# BulbCommander2.net
KiCad netlist of a schematic drawn in Altium Designer
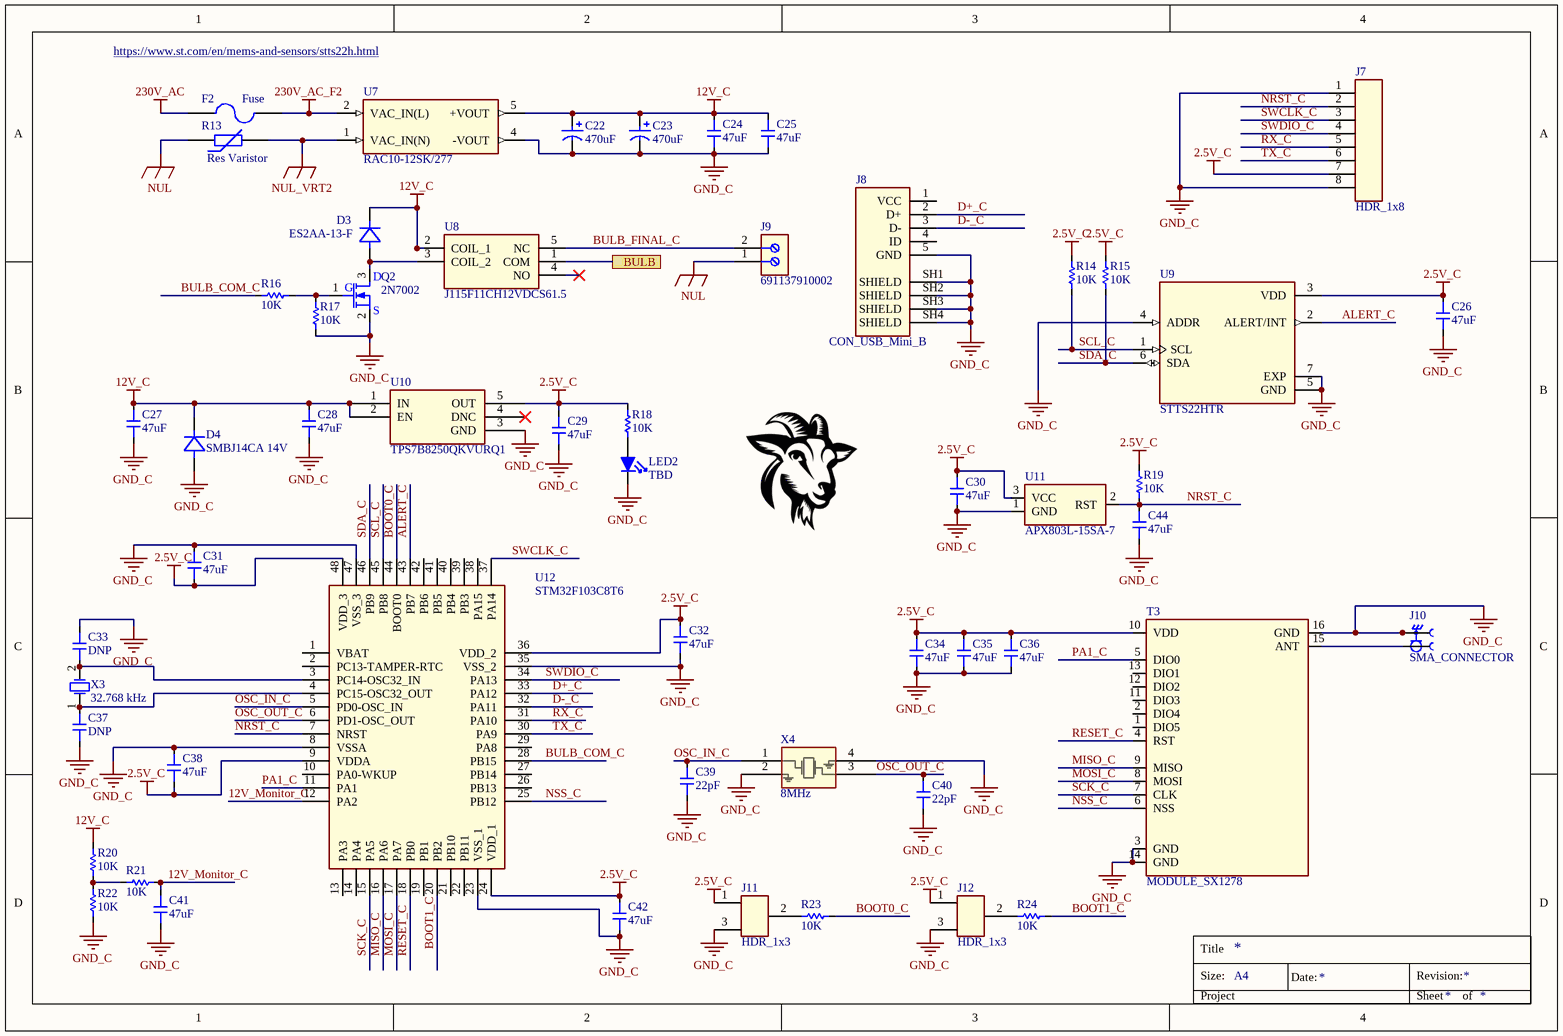
[diagram p0: BulbCommander2.SchDoc]

(export (version "E")
  (design (tool "Eeschema 10.0.6"))
  (components
    (comp (ref "C22")
      (value "470uF")
      (footprint "WCAP-ASLL_D16H17")
      (description "Capacitor_Pol_470uF")
      (fields (field (name "Comment") "Cap Pol1") (field (name "PUBLISHER") "Altium Limited"))
      (libsource (lib "BulbCommander") (part "Capacitor_Pol_470uF"))
    )
    (comp (ref "C23")
      (value "470uF")
      (footprint "WCAP-ASLL_D16H17")
      (description "Capacitor_Pol_470uF")
      (fields (field (name "Comment") "Cap Pol1") (field (name "PUBLISHER") "Altium Limited"))
      (libsource (lib "BulbCommander") (part "Capacitor_Pol_470uF"))
    )
    (comp (ref "C24")
      (value "47uF")
      (footprint "2220")
      (description "CAP CER 47uF 20% 35V X7R 2220")
      (fields (field (name "MFR") "TBD"))
      (libsource (lib "BulbCommander") (part "Capacitor_47uF_2220"))
    )
    (comp (ref "C25")
      (value "47uF")
      (footprint "2220")
      (description "CAP CER 47uF 20% 35V X7R 2220")
      (fields (field (name "MFR") "TBD"))
      (libsource (lib "BulbCommander") (part "Capacitor_47uF_2220"))
    )
    (comp (ref "C26")
      (value "47uF")
      (footprint "CASE0603")
      (description "CAP CER 47uF 20% 35V X7R 2220")
      (fields (field (name "MFR") "TBD"))
      (libsource (lib "BulbCommander") (part "Capacitor_47uF_1206"))
    )
    (comp (ref "C27")
      (value "47uF")
      (footprint "1206")
      (description "CAP CER 47uF 20% 35V X7R 2220")
      (fields (field (name "MFR") "TBD"))
      (libsource (lib "BulbCommander") (part "Capacitor_47uF_1206"))
    )
    (comp (ref "C28")
      (value "47uF")
      (footprint "1206")
      (description "CAP CER 47uF 20% 35V X7R 2220")
      (fields (field (name "MFR") "TBD"))
      (libsource (lib "BulbCommander") (part "Capacitor_47uF_1206"))
    )
    (comp (ref "C29")
      (value "47uF")
      (footprint "1206")
      (description "CAP CER 47uF 20% 35V X7R 2220")
      (fields (field (name "MFR") "TBD"))
      (libsource (lib "BulbCommander") (part "Capacitor_47uF_1206"))
    )
    (comp (ref "C30")
      (value "47uF")
      (footprint "CASE0603")
      (description "CAP CER 47uF 20% 35V X7R 2220")
      (fields (field (name "MFR") "TBD"))
      (libsource (lib "BulbCommander") (part "Capacitor_47uF_1206"))
    )
    (comp (ref "C31")
      (value "47uF")
      (footprint "CASE0603")
      (description "CAP CER 47uF 20% 35V X7R 2220")
      (fields (field (name "MFR") "TBD"))
      (libsource (lib "BulbCommander") (part "Capacitor_47uF_1206"))
    )
    (comp (ref "C32")
      (value "47uF")
      (footprint "CASE0603")
      (description "CAP CER 47uF 20% 35V X7R 2220")
      (fields (field (name "MFR") "TBD"))
      (libsource (lib "BulbCommander") (part "Capacitor_47uF_1206"))
    )
    (comp (ref "C33")
      (value "DNP")
      (footprint "CASE0603")
      (description "CAP CER 47uF 20% 35V X7R 2220")
      (fields (field (name "MFR") "TBD"))
      (libsource (lib "BulbCommander") (part "Capacitor_47uF_0603"))
    )
    (comp (ref "C34")
      (value "47uF")
      (footprint "CASE0603")
      (description "CAP CER 47uF 20% 35V X7R 2220")
      (fields (field (name "MFR") "TBD"))
      (libsource (lib "BulbCommander") (part "Capacitor_47uF_1206"))
    )
    (comp (ref "C35")
      (value "47uF")
      (footprint "CASE0603")
      (description "CAP CER 47uF 20% 35V X7R 2220")
      (fields (field (name "MFR") "TBD"))
      (libsource (lib "BulbCommander") (part "Capacitor_47uF_1206"))
    )
    (comp (ref "C36")
      (value "47uF")
      (footprint "CASE0603")
      (description "CAP CER 47uF 20% 35V X7R 2220")
      (fields (field (name "MFR") "TBD"))
      (libsource (lib "BulbCommander") (part "Capacitor_47uF_1206"))
    )
    (comp (ref "C37")
      (value "DNP")
      (footprint "CASE0603")
      (description "CAP CER 47uF 20% 35V X7R 2220")
      (fields (field (name "MFR") "TBD"))
      (libsource (lib "BulbCommander") (part "Capacitor_47uF_0603"))
    )
    (comp (ref "C38")
      (value "47uF")
      (footprint "CASE0603")
      (description "CAP CER 47uF 20% 35V X7R 2220")
      (fields (field (name "MFR") "TBD"))
      (libsource (lib "BulbCommander") (part "Capacitor_47uF_1206"))
    )
    (comp (ref "C39")
      (value "22pF")
      (footprint "CASE0603")
      (description "CAP CER 47uF 20% 35V X7R 2220")
      (fields (field (name "MFR") "TBD"))
      (libsource (lib "BulbCommander") (part "Capacitor_47uF_1206"))
    )
    (comp (ref "C40")
      (value "22pF")
      (footprint "CASE0603")
      (description "CAP CER 47uF 20% 35V X7R 2220")
      (fields (field (name "MFR") "TBD"))
      (libsource (lib "BulbCommander") (part "Capacitor_47uF_1206"))
    )
    (comp (ref "C41")
      (value "47uF")
      (footprint "CASE0603")
      (description "CAP CER 47uF 20% 35V X7R 2220")
      (fields (field (name "MFR") "TBD"))
      (libsource (lib "BulbCommander") (part "Capacitor_47uF_1206"))
    )
    (comp (ref "C42")
      (value "47uF")
      (footprint "CASE0603")
      (description "CAP CER 47uF 20% 35V X7R 2220")
      (fields (field (name "MFR") "TBD"))
      (libsource (lib "BulbCommander") (part "Capacitor_47uF_1206"))
    )
    (comp (ref "C44")
      (value "47uF")
      (footprint "CASE0603")
      (description "CAP CER 47uF 20% 35V X7R 2220")
      (fields (field (name "MFR") "TBD"))
      (libsource (lib "BulbCommander") (part "Capacitor_47uF_1206"))
    )
    (comp (ref "D3")
      (value "ES2AA-13-F")
      (footprint "SMA_DIODE")
      (description "DIODE STANDARD 50V 2A SMA")
      (fields (field (name "MFR") "Diodes Incoprated"))
      (libsource (lib "BulbCommander") (part "Diode_SMA"))
    )
    (comp (ref "D4")
      (value "SMBJ14CA 14V")
      (footprint "SMBJSeries_LTF-M")
      (description "SMBJ14CA TVS DIODE 14V")
      (libsource (lib "BulbCommander") (part "Diode_SMBJ14CA"))
    )
    (comp (ref "F2")
      (value "Fuse")
      (footprint "FUSE")
      (fields (field (name "PUBLISHER") "Altium Limited"))
      (libsource (lib "BulbCommander") (part "Fuse"))
    )
    (comp (ref "J7")
      (value "HDR_1x8")
      (footprint "Header_1x8_2.54_Male")
      (description "HDR MALE 2.54MM PCB")
      (fields (field (name "MFR") "Wurth"))
      (libsource (lib "BulbCommander") (part "HDR_1x8"))
    )
    (comp (ref "J8")
      (value "CON_USB_Mini_B")
      (footprint "CUI_UJ2-MBH-4-SMT")
      (description "USB B mini")
      (fields (field (name "MFR") "Same Sky"))
      (libsource (lib "BulbCommander") (part "CON_USB_Mini_B"))
    )
    (comp (ref "J9")
      (value "691137910002")
      (footprint "691137910002")
      (description "TERM BLOCK 2P HORIZON 7.5MM PCB")
      (fields (field (name "MFR") "Wurth"))
      (libsource (lib "BulbCommander") (part "CON_1x2"))
    )
    (comp (ref "J10")
      (value "SMA_CONNECTOR")
      (footprint "LPRS_SMA_CONNECTOR")
      (description "Straight SMA Connector")
      (fields (field (name "MP") "altium_native_batch"))
      (libsource (lib "BulbCommander") (part "SMA_CONNECTOR"))
    )
    (comp (ref "J11")
      (value "HDR_1x3")
      (footprint "Header_1x3_2.54_Male")
      (description "HDR MALE 3 x 2.54MM PCB")
      (fields (field (name "MFR") "Wurth"))
      (libsource (lib "BulbCommander") (part "HDR_1x3"))
    )
    (comp (ref "J12")
      (value "HDR_1x3")
      (footprint "Header_1x3_2.54_Male")
      (description "HDR MALE 3 x 2.54MM PCB")
      (fields (field (name "MFR") "Wurth"))
      (libsource (lib "BulbCommander") (part "HDR_1x3"))
    )
    (comp (ref "LED2")
      (value "TBD")
      (footprint "CASE0603")
      (description "Typical INFRARED GaAs LED")
      (libsource (lib "BulbCommander") (part "LED"))
    )
    (comp (ref "Q2")
      (value "2N7002")
      (footprint "SOT23-3")
      (description "MOSFET N-CH 60V 280MA SOT23-3")
      (fields (field (name "MFR") "Microchip"))
      (libsource (lib "BulbCommander") (part "Transistor_NMOS"))
    )
    (comp (ref "R13")
      (value "Res Varistor")
      (footprint "AXIAL-0.3")
      (description "Varistor (Voltage-Sensitive Resistor)")
      (fields (field (name "PUBLISHER") "Altium Limited"))
      (libsource (lib "BulbCommander") (part "Res Varistor"))
    )
    (comp (ref "R14")
      (value "10K")
      (footprint "CASE0603")
      (description "RES 10K 1% 1/10W 0603")
      (fields (field (name "MFR") "YAGEO"))
      (libsource (lib "BulbCommander") (part "Resistor_10K_0603"))
    )
    (comp (ref "R15")
      (value "10K")
      (footprint "CASE0603")
      (description "RES 10K 1% 1/10W 0603")
      (fields (field (name "MFR") "YAGEO"))
      (libsource (lib "BulbCommander") (part "Resistor_10K_0603"))
    )
    (comp (ref "R16")
      (value "10K")
      (footprint "CASE0603")
      (description "RES 10K 1% 1/10W 0603")
      (fields (field (name "MFR") "YAGEO"))
      (libsource (lib "BulbCommander") (part "Resistor_10K_0603"))
    )
    (comp (ref "R17")
      (value "10K")
      (footprint "CASE0603")
      (description "RES 10K 1% 1/10W 0603")
      (fields (field (name "MFR") "YAGEO"))
      (libsource (lib "BulbCommander") (part "Resistor_10K_0603"))
    )
    (comp (ref "R18")
      (value "10K")
      (footprint "CASE0603")
      (description "RES 10K 1% 1/10W 0603")
      (fields (field (name "MFR") "YAGEO"))
      (libsource (lib "BulbCommander") (part "Resistor_10K_0603"))
    )
    (comp (ref "R19")
      (value "10K")
      (footprint "CASE0603")
      (description "RES 10K 1% 1/10W 0603")
      (fields (field (name "MFR") "YAGEO"))
      (libsource (lib "BulbCommander") (part "Resistor_10K_0603"))
    )
    (comp (ref "R20")
      (value "10K")
      (footprint "CASE0603")
      (description "RES 10K 1% 1/10W 0603")
      (fields (field (name "MFR") "YAGEO"))
      (libsource (lib "BulbCommander") (part "Resistor_10K_0603"))
    )
    (comp (ref "R21")
      (value "10K")
      (footprint "CASE0603")
      (description "RES 10K 1% 1/10W 0603")
      (fields (field (name "MFR") "YAGEO"))
      (libsource (lib "BulbCommander") (part "Resistor_10K_0603"))
    )
    (comp (ref "R22")
      (value "10K")
      (footprint "CASE0603")
      (description "RES 10K 1% 1/10W 0603")
      (fields (field (name "MFR") "YAGEO"))
      (libsource (lib "BulbCommander") (part "Resistor_10K_0603"))
    )
    (comp (ref "R23")
      (value "10K")
      (footprint "CASE0603")
      (description "RES 10K 1% 1/10W 0603")
      (fields (field (name "MFR") "YAGEO"))
      (libsource (lib "BulbCommander") (part "Resistor_10K_0603"))
    )
    (comp (ref "R24")
      (value "10K")
      (footprint "CASE0603")
      (description "RES 10K 1% 1/10W 0603")
      (fields (field (name "MFR") "YAGEO"))
      (libsource (lib "BulbCommander") (part "Resistor_10K_0603"))
    )
    (comp (ref "T3")
      (value "MODULE_SX1278")
      (footprint "LORA SX1278")
      (description "MODULE_SX1278 LORA 433 MHz")
      (fields (field (name "MFR") "LORA"))
      (libsource (lib "BulbCommander") (part "MODULE_SX1278"))
    )
    (comp (ref "U7")
      (value "RAC10-12SK/277")
      (footprint "CONV_RAC10-12SK/277")
      (description "AC/DC CONVERTER 12V 10W")
      (fields (field (name "MFR") "RECOM"))
      (libsource (lib "BulbCommander") (part "CONV_RAC10-12SK/277"))
    )
    (comp (ref "U8")
      (value "J115F11CH12VDCS61.5")
      (footprint "J115F11CH12VDCS615U")
      (description "RELAY GEN PURPOSE SPDT 50A 12V")
      (fields (field (name "MFR") "CIT Relay and Switch"))
      (libsource (lib "BulbCommander") (part "RELAY_J115F11CH12VDCS61.5"))
    )
    (comp (ref "U9")
      (value "STTS22HTR")
      (footprint "Sensor_6-UDFN")
      (description "Low-voltage, ultralow-power, 0.5°C accuracy I²C/SMBus 3.0 temperature sensor")
      (fields (field (name "MFR") "STMicroelectronics"))
      (libsource (lib "BulbCommander") (part "SENSOR_STTS22HTR"))
    )
    (comp (ref "U10")
      (value "TPS7B8250QKVURQ1")
      (footprint "SOT_QKVURQ1_TEX")
      (fields (field (name "MFR") "Texas Instruments"))
      (libsource (lib "BulbCommander") (part "CONV_LDO_TPS7B8250QKVURQ1"))
    )
    (comp (ref "U11")
      (value "APX803L-15SA-7")
      (footprint "SOT23-3")
      (description "Supervisor Open Drain or Open Collector 1 Channel SOT-23-3")
      (fields (field (name "MFR") "Diodes Incorporated"))
      (libsource (lib "BulbCommander") (part "IC_APX803L-15SA-7"))
    )
    (comp (ref "U12")
      (value "STM32F103C8T6")
      (footprint "QFP50P900X900X160-48N")
      (description "IC MCU 32BIT 64KB FLASH 48LQFP")
      (fields (field (name "MFR") "STMicroelectronics"))
      (libsource (lib "BulbCommander") (part "IC_STM32F103C8T6"))
    )
    (comp (ref "X3")
      (value "32.768 kHz")
      (footprint "XTAL_ECS-.327-12.5-34B-C-TR")
      (description "32.768 kHz ±10ppm Crystal 12.5pF 70 kOhms 2-SMD, No Lead")
      (fields (field (name "MFR") "ECS"))
      (libsource (lib "BulbCommander") (part "Crystal_ECS-.327-12.5-34B-C-TR"))
    )
    (comp (ref "X4")
      (value "8MHz")
      (footprint "XTAL4P_ABM3B_ABR")
      (description "8 MHz Crystal")
      (fields (field (name "MFR") "Abracon"))
      (libsource (lib "BulbCommander") (part "ABM3B-8.000MHZ-10-1UT"))
    )
  )
  (nets
    (net (code "1") (name "/12V_Monitor_C") (class "Default")
      (node (ref "C41") (pin "1") (pinfunction "1_1") (pintype "passive"))
      (node (ref "R21") (pin "2") (pinfunction "2_2") (pintype "passive"))
      (node (ref "U12") (pin "12") (pinfunction "PA2_12") (pintype "passive"))
    )
    (net (code "2") (name "/ALERT_C") (class "Default")
      (node (ref "U12") (pin "43") (pinfunction "PB7_43") (pintype "passive"))
      (node (ref "U9") (pin "2") (pinfunction "ALERT/INT_2") (pintype "output"))
    )
    (net (code "3") (name "/BOOT0_C") (class "Default")
      (node (ref "R23") (pin "1") (pinfunction "1_1") (pintype "passive"))
      (node (ref "U12") (pin "44") (pinfunction "BOOT0_44") (pintype "passive"))
    )
    (net (code "4") (name "/BOOT1_C") (class "Default")
      (node (ref "R24") (pin "1") (pinfunction "1_1") (pintype "passive"))
      (node (ref "U12") (pin "20") (pinfunction "PB2_20") (pintype "passive"))
    )
    (net (code "5") (name "/BULB") (class "Default")
      (node (ref "U8") (pin "1") (pinfunction "COM_1") (pintype "passive"))
    )
    (net (code "6") (name "/BULB_COM_C") (class "Default")
      (node (ref "R16") (pin "2") (pinfunction "2_2") (pintype "passive"))
      (node (ref "U12") (pin "28") (pinfunction "PB15_28") (pintype "passive"))
    )
    (net (code "7") (name "/BULB_FINAL_C") (class "Default")
      (node (ref "J9") (pin "2") (pinfunction "2_2") (pintype "passive"))
      (node (ref "U8") (pin "5") (pinfunction "NC_5") (pintype "passive"))
    )
    (net (code "8") (name "/D+_C") (class "Default")
      (node (ref "J8") (pin "2") (pinfunction "D+_2") (pintype "passive"))
      (node (ref "U12") (pin "33") (pinfunction "PA12_33") (pintype "passive"))
    )
    (net (code "9") (name "/D-_C") (class "Default")
      (node (ref "J8") (pin "3") (pinfunction "D-_3") (pintype "passive"))
      (node (ref "U12") (pin "32") (pinfunction "PA11_32") (pintype "passive"))
    )
    (net (code "10") (name "/MISO_C") (class "Default")
      (node (ref "T3") (pin "9") (pinfunction "MISO_9") (pintype "passive"))
      (node (ref "U12") (pin "16") (pinfunction "PA6_16") (pintype "passive"))
    )
    (net (code "11") (name "/MOSI_C") (class "Default")
      (node (ref "T3") (pin "8") (pinfunction "MOSI_8") (pintype "passive"))
      (node (ref "U12") (pin "17") (pinfunction "PA7_17") (pintype "passive"))
    )
    (net (code "12") (name "/NRST_C") (class "Default")
      (node (ref "C44") (pin "2") (pinfunction "2_2") (pintype "passive"))
      (node (ref "J7") (pin "2") (pinfunction "2_2") (pintype "passive"))
      (node (ref "R19") (pin "1") (pinfunction "1_1") (pintype "passive"))
      (node (ref "U11") (pin "2") (pinfunction "RST_2") (pintype "passive"))
      (node (ref "U12") (pin "7") (pinfunction "NRST_7") (pintype "passive"))
    )
    (net (code "13") (name "/NSS_C") (class "Default")
      (node (ref "T3") (pin "6") (pinfunction "NSS_6") (pintype "passive"))
      (node (ref "U12") (pin "25") (pinfunction "PB12_25") (pintype "passive"))
    )
    (net (code "14") (name "/OSC_IN_C") (class "Default")
      (node (ref "C39") (pin "1") (pinfunction "1_1") (pintype "passive"))
      (node (ref "U12") (pin "5") (pinfunction "PD0-OSC_IN_5") (pintype "passive"))
      (node (ref "X4") (pin "1") (pinfunction "1_1") (pintype "passive"))
    )
    (net (code "15") (name "/OSC_OUT_C") (class "Default")
      (node (ref "C40") (pin "1") (pinfunction "1_1") (pintype "passive"))
      (node (ref "U12") (pin "6") (pinfunction "PD1-OSC_OUT_6") (pintype "passive"))
      (node (ref "X4") (pin "3") (pinfunction "3_3") (pintype "passive"))
    )
    (net (code "16") (name "/PA1_C") (class "Default")
      (node (ref "T3") (pin "5") (pinfunction "DIO0_5") (pintype "passive"))
      (node (ref "U12") (pin "11") (pinfunction "PA1_11") (pintype "passive"))
    )
    (net (code "17") (name "/RESET_C") (class "Default")
      (node (ref "T3") (pin "4") (pinfunction "RST_4") (pintype "passive"))
      (node (ref "U12") (pin "18") (pinfunction "PB0_18") (pintype "passive"))
    )
    (net (code "18") (name "/RX_C") (class "Default")
      (node (ref "J7") (pin "5") (pinfunction "5_5") (pintype "passive"))
      (node (ref "U12") (pin "31") (pinfunction "PA10_31") (pintype "passive"))
    )
    (net (code "19") (name "/SCK_C") (class "Default")
      (node (ref "T3") (pin "7") (pinfunction "CLK_7") (pintype "passive"))
      (node (ref "U12") (pin "15") (pinfunction "PA5_15") (pintype "passive"))
    )
    (net (code "20") (name "/SCL_C") (class "Default")
      (node (ref "R14") (pin "1") (pinfunction "1_1") (pintype "passive"))
      (node (ref "U12") (pin "45") (pinfunction "PB8_45") (pintype "passive"))
      (node (ref "U9") (pin "1") (pinfunction "SCL_1") (pintype "input"))
    )
    (net (code "21") (name "/SDA_C") (class "Default")
      (node (ref "R15") (pin "1") (pinfunction "1_1") (pintype "passive"))
      (node (ref "U12") (pin "46") (pinfunction "PB9_46") (pintype "passive"))
      (node (ref "U9") (pin "6") (pinfunction "SDA_6") (pintype "bidirectional"))
    )
    (net (code "22") (name "/SWCLK_C") (class "Default")
      (node (ref "J7") (pin "3") (pinfunction "3_3") (pintype "passive"))
      (node (ref "U12") (pin "37") (pinfunction "PA14_37") (pintype "passive"))
    )
    (net (code "23") (name "/SWDIO_C") (class "Default")
      (node (ref "J7") (pin "4") (pinfunction "4_4") (pintype "passive"))
      (node (ref "U12") (pin "34") (pinfunction "PA13_34") (pintype "passive"))
    )
    (net (code "24") (name "/TX_C") (class "Default")
      (node (ref "J7") (pin "6") (pinfunction "6_6") (pintype "passive"))
      (node (ref "U12") (pin "30") (pinfunction "PA9_30") (pintype "passive"))
    )
    (net (code "25") (name "2.5V_C") (class "Default")
      (node (ref "C26") (pin "2") (pinfunction "2_2") (pintype "passive"))
      (node (ref "C29") (pin "2") (pinfunction "2_2") (pintype "passive"))
      (node (ref "C30") (pin "2") (pinfunction "2_2") (pintype "passive"))
      (node (ref "C31") (pin "1") (pinfunction "1_1") (pintype "passive"))
      (node (ref "C32") (pin "2") (pinfunction "2_2") (pintype "passive"))
      (node (ref "C34") (pin "2") (pinfunction "2_2") (pintype "passive"))
      (node (ref "C35") (pin "2") (pinfunction "2_2") (pintype "passive"))
      (node (ref "C36") (pin "2") (pinfunction "2_2") (pintype "passive"))
      (node (ref "C38") (pin "2") (pinfunction "2_2") (pintype "passive"))
      (node (ref "C42") (pin "2") (pinfunction "2_2") (pintype "passive"))
      (node (ref "J11") (pin "1") (pinfunction "1_1") (pintype "passive"))
      (node (ref "J12") (pin "1") (pinfunction "1_1") (pintype "passive"))
      (node (ref "J7") (pin "7") (pinfunction "7_7") (pintype "passive"))
      (node (ref "R14") (pin "2") (pinfunction "2_2") (pintype "passive"))
      (node (ref "R15") (pin "2") (pinfunction "2_2") (pintype "passive"))
      (node (ref "R18") (pin "2") (pinfunction "2_2") (pintype "passive"))
      (node (ref "R19") (pin "2") (pinfunction "2_2") (pintype "passive"))
      (node (ref "T3") (pin "10") (pinfunction "VDD_10") (pintype "passive"))
      (node (ref "U10") (pin "5") (pinfunction "OUT_5") (pintype "passive"))
      (node (ref "U11") (pin "3") (pinfunction "VCC_3") (pintype "passive"))
      (node (ref "U12") (pin "24") (pinfunction "VDD_1_24") (pintype "passive"))
      (node (ref "U12") (pin "36") (pinfunction "VDD_2_36") (pintype "passive"))
      (node (ref "U12") (pin "48") (pinfunction "VDD_3_48") (pintype "passive"))
      (node (ref "U12") (pin "9") (pinfunction "VDDA_9") (pintype "passive"))
      (node (ref "U9") (pin "3") (pinfunction "VDD_3") (pintype "power_in"))
    )
    (net (code "26") (name "12V_C") (class "Default")
      (node (ref "C22") (pin "1") (pinfunction "1_1") (pintype "passive"))
      (node (ref "C23") (pin "1") (pinfunction "1_1") (pintype "passive"))
      (node (ref "C24") (pin "2") (pinfunction "2_2") (pintype "passive"))
      (node (ref "C25") (pin "2") (pinfunction "2_2") (pintype "passive"))
      (node (ref "C27") (pin "2") (pinfunction "2_2") (pintype "passive"))
      (node (ref "C28") (pin "2") (pinfunction "2_2") (pintype "passive"))
      (node (ref "D3") (pin "1") (pinfunction "1_1") (pintype "passive"))
      (node (ref "D4") (pin "1") (pinfunction "1_1") (pintype "passive"))
      (node (ref "R20") (pin "2") (pinfunction "2_2") (pintype "passive"))
      (node (ref "U10") (pin "1") (pinfunction "IN_1") (pintype "passive"))
      (node (ref "U10") (pin "2") (pinfunction "EN_2") (pintype "passive"))
      (node (ref "U7") (pin "5") (pinfunction "+VOUT_5") (pintype "output"))
      (node (ref "U8") (pin "2") (pinfunction "COIL_1_2") (pintype "passive"))
    )
    (net (code "27") (name "230V_AC") (class "Default")
      (node (ref "F2") (pin "1") (pinfunction "1_1") (pintype "passive"))
    )
    (net (code "28") (name "230V_AC_F2") (class "Default")
      (node (ref "F2") (pin "2") (pinfunction "2_2") (pintype "passive"))
      (node (ref "U7") (pin "2") (pinfunction "VAC_IN(L)_2") (pintype "input"))
    )
    (net (code "29") (name "GND_C") (class "Default")
      (node (ref "C22") (pin "2") (pinfunction "2_2") (pintype "passive"))
      (node (ref "C23") (pin "2") (pinfunction "2_2") (pintype "passive"))
      (node (ref "C24") (pin "1") (pinfunction "1_1") (pintype "passive"))
      (node (ref "C25") (pin "1") (pinfunction "1_1") (pintype "passive"))
      (node (ref "C26") (pin "1") (pinfunction "1_1") (pintype "passive"))
      (node (ref "C27") (pin "1") (pinfunction "1_1") (pintype "passive"))
      (node (ref "C28") (pin "1") (pinfunction "1_1") (pintype "passive"))
      (node (ref "C29") (pin "1") (pinfunction "1_1") (pintype "passive"))
      (node (ref "C30") (pin "1") (pinfunction "1_1") (pintype "passive"))
      (node (ref "C31") (pin "2") (pinfunction "2_2") (pintype "passive"))
      (node (ref "C32") (pin "1") (pinfunction "1_1") (pintype "passive"))
      (node (ref "C33") (pin "2") (pinfunction "2_2") (pintype "passive"))
      (node (ref "C34") (pin "1") (pinfunction "1_1") (pintype "passive"))
      (node (ref "C35") (pin "1") (pinfunction "1_1") (pintype "passive"))
      (node (ref "C36") (pin "1") (pinfunction "1_1") (pintype "passive"))
      (node (ref "C37") (pin "2") (pinfunction "2_2") (pintype "passive"))
      (node (ref "C38") (pin "1") (pinfunction "1_1") (pintype "passive"))
      (node (ref "C39") (pin "2") (pinfunction "2_2") (pintype "passive"))
      (node (ref "C40") (pin "2") (pinfunction "2_2") (pintype "passive"))
      (node (ref "C41") (pin "2") (pinfunction "2_2") (pintype "passive"))
      (node (ref "C42") (pin "1") (pinfunction "1_1") (pintype "passive"))
      (node (ref "C44") (pin "1") (pinfunction "1_1") (pintype "passive"))
      (node (ref "D4") (pin "2") (pinfunction "2_2") (pintype "passive"))
      (node (ref "J10") (pin "G1") (pinfunction "2_G1") (pintype "passive"))
      (node (ref "J10") (pin "G2") (pinfunction "2_G2") (pintype "passive"))
      (node (ref "J10") (pin "G3") (pinfunction "2_G3") (pintype "passive"))
      (node (ref "J10") (pin "G4") (pinfunction "2_G4") (pintype "passive"))
      (node (ref "J11") (pin "3") (pinfunction "3_3") (pintype "passive"))
      (node (ref "J12") (pin "3") (pinfunction "3_3") (pintype "passive"))
      (node (ref "J7") (pin "1") (pinfunction "1_1") (pintype "passive"))
      (node (ref "J7") (pin "8") (pinfunction "8_8") (pintype "passive"))
      (node (ref "J8") (pin "5") (pinfunction "GND_5") (pintype "passive"))
      (node (ref "J8") (pin "SH1") (pinfunction "SHIELD_SH1") (pintype "passive"))
      (node (ref "J8") (pin "SH2") (pinfunction "SHIELD_SH2") (pintype "passive"))
      (node (ref "J8") (pin "SH3") (pinfunction "SHIELD_SH3") (pintype "passive"))
      (node (ref "J8") (pin "SH4") (pinfunction "SHIELD_SH4") (pintype "passive"))
      (node (ref "LED2") (pin "2") (pinfunction "K_2") (pintype "passive"))
      (node (ref "Q2") (pin "2") (pinfunction "S_2") (pintype "passive"))
      (node (ref "R17") (pin "1") (pinfunction "1_1") (pintype "passive"))
      (node (ref "R22") (pin "1") (pinfunction "1_1") (pintype "passive"))
      (node (ref "T3") (pin "14") (pinfunction "GND_14") (pintype "passive"))
      (node (ref "T3") (pin "16") (pinfunction "GND_16") (pintype "passive"))
      (node (ref "T3") (pin "3") (pinfunction "GND_3") (pintype "passive"))
      (node (ref "U10") (pin "3") (pinfunction "GND_3") (pintype "power_in"))
      (node (ref "U11") (pin "1") (pinfunction "GND_1") (pintype "passive"))
      (node (ref "U12") (pin "23") (pinfunction "VSS_1_23") (pintype "passive"))
      (node (ref "U12") (pin "35") (pinfunction "VSS_2_35") (pintype "passive"))
      (node (ref "U12") (pin "47") (pinfunction "VSS_3_47") (pintype "passive"))
      (node (ref "U12") (pin "8") (pinfunction "VSSA_8") (pintype "passive"))
      (node (ref "U7") (pin "4") (pinfunction "-VOUT_4") (pintype "output"))
      (node (ref "U9") (pin "4") (pinfunction "ADDR_4") (pintype "input"))
      (node (ref "U9") (pin "5") (pinfunction "GND_5") (pintype "power_in"))
      (node (ref "U9") (pin "7") (pinfunction "EXP_7") (pintype "passive"))
      (node (ref "X4") (pin "2") (pinfunction "2_2") (pintype "passive"))
      (node (ref "X4") (pin "4") (pinfunction "4_4") (pintype "passive"))
    )
    (net (code "30") (name "NUL") (class "Default")
      (node (ref "J9") (pin "1") (pinfunction "1_1") (pintype "passive"))
      (node (ref "R13") (pin "1") (pinfunction "1_1") (pintype "passive"))
    )
    (net (code "31") (name "NUL_VRT2") (class "Default")
      (node (ref "R13") (pin "2") (pinfunction "2_2") (pintype "passive"))
      (node (ref "U7") (pin "1") (pinfunction "VAC_IN(N)_1") (pintype "input"))
    )
    (net (code "32") (name "Net-(J11-Pad2)") (class "Default")
      (node (ref "J11") (pin "2") (pinfunction "2_2") (pintype "passive"))
      (node (ref "R23") (pin "2") (pinfunction "2_2") (pintype "passive"))
    )
    (net (code "33") (name "Net-(J12-Pad2)") (class "Default")
      (node (ref "J12") (pin "2") (pinfunction "2_2") (pintype "passive"))
      (node (ref "R24") (pin "2") (pinfunction "2_2") (pintype "passive"))
    )
    (net (code "34") (name "Net-(LED2-A)") (class "Default")
      (node (ref "LED2") (pin "1") (pinfunction "A_1") (pintype "passive"))
      (node (ref "R18") (pin "1") (pinfunction "1_1") (pintype "passive"))
    )
    (net (code "35") (name "Net-(Q2-D)") (class "Default")
      (node (ref "D3") (pin "2") (pinfunction "2_2") (pintype "passive"))
      (node (ref "Q2") (pin "3") (pinfunction "D_3") (pintype "passive"))
      (node (ref "U8") (pin "3") (pinfunction "COIL_2_3") (pintype "passive"))
    )
    (net (code "36") (name "Net-(Q2-G)") (class "Default")
      (node (ref "Q2") (pin "1") (pinfunction "G_1") (pintype "passive"))
      (node (ref "R16") (pin "1") (pinfunction "1_1") (pintype "passive"))
      (node (ref "R17") (pin "2") (pinfunction "2_2") (pintype "passive"))
    )
    (net (code "37") (name "Net-(R20-Pad1)") (class "Default")
      (node (ref "R20") (pin "1") (pinfunction "1_1") (pintype "passive"))
      (node (ref "R21") (pin "1") (pinfunction "1_1") (pintype "passive"))
      (node (ref "R22") (pin "2") (pinfunction "2_2") (pintype "passive"))
    )
    (net (code "38") (name "Net-(T3-ANT)") (class "Default")
      (node (ref "J10") (pin "1") (pinfunction "1_1") (pintype "passive"))
      (node (ref "T3") (pin "15") (pinfunction "ANT_15") (pintype "passive"))
    )
    (net (code "39") (name "Net-(U12-PC14-OSC32_IN)") (class "Default")
      (node (ref "C33") (pin "1") (pinfunction "1_1") (pintype "passive"))
      (node (ref "U12") (pin "3") (pinfunction "PC14-OSC32_IN_3") (pintype "passive"))
      (node (ref "X3") (pin "2") (pinfunction "OSC2_2") (pintype "passive"))
    )
    (net (code "40") (name "Net-(U12-PC15-OSC32_OUT)") (class "Default")
      (node (ref "C37") (pin "1") (pinfunction "1_1") (pintype "passive"))
      (node (ref "U12") (pin "4") (pinfunction "PC15-OSC32_OUT_4") (pintype "passive"))
      (node (ref "X3") (pin "1") (pinfunction "OSC1_1") (pintype "passive"))
    )
    (net (code "41") (name "unconnected-(J8-ID-Pad4)") (class "Default")
      (node (ref "J8") (pin "4") (pinfunction "ID_4") (pintype "passive"))
    )
    (net (code "42") (name "unconnected-(J8-VCC-Pad1)") (class "Default")
      (node (ref "J8") (pin "1") (pinfunction "VCC_1") (pintype "passive"))
    )
    (net (code "43") (name "unconnected-(T3-DIO1-Pad13)") (class "Default")
      (node (ref "T3") (pin "13") (pinfunction "DIO1_13") (pintype "passive"))
    )
    (net (code "44") (name "unconnected-(T3-DIO2-Pad12)") (class "Default")
      (node (ref "T3") (pin "12") (pinfunction "DIO2_12") (pintype "passive"))
    )
    (net (code "45") (name "unconnected-(T3-DIO3-Pad11)") (class "Default")
      (node (ref "T3") (pin "11") (pinfunction "DIO3_11") (pintype "passive"))
    )
    (net (code "46") (name "unconnected-(T3-DIO4-Pad2)") (class "Default")
      (node (ref "T3") (pin "2") (pinfunction "DIO4_2") (pintype "passive"))
    )
    (net (code "47") (name "unconnected-(T3-DIO5-Pad1)") (class "Default")
      (node (ref "T3") (pin "1") (pinfunction "DIO5_1") (pintype "passive"))
    )
    (net (code "48") (name "unconnected-(U8-NO-Pad4)") (class "Default")
      (node (ref "U8") (pin "4") (pinfunction "NO_4") (pintype "passive+no_connect"))
    )
    (net (code "49") (name "unconnected-(U10-DNC-Pad4)") (class "Default")
      (node (ref "U10") (pin "4") (pinfunction "DNC_4") (pintype "passive+no_connect"))
    )
    (net (code "50") (name "unconnected-(U12-PA0-WKUP-Pad10)") (class "Default")
      (node (ref "U12") (pin "10") (pinfunction "PA0-WKUP_10") (pintype "passive"))
    )
    (net (code "51") (name "unconnected-(U12-PA3-Pad13)") (class "Default")
      (node (ref "U12") (pin "13") (pinfunction "PA3_13") (pintype "passive"))
    )
    (net (code "52") (name "unconnected-(U12-PA4-Pad14)") (class "Default")
      (node (ref "U12") (pin "14") (pinfunction "PA4_14") (pintype "passive"))
    )
    (net (code "53") (name "unconnected-(U12-PA8-Pad29)") (class "Default")
      (node (ref "U12") (pin "29") (pinfunction "PA8_29") (pintype "passive"))
    )
    (net (code "54") (name "unconnected-(U12-PA15-Pad38)") (class "Default")
      (node (ref "U12") (pin "38") (pinfunction "PA15_38") (pintype "passive"))
    )
    (net (code "55") (name "unconnected-(U12-PB1-Pad19)") (class "Default")
      (node (ref "U12") (pin "19") (pinfunction "PB1_19") (pintype "passive"))
    )
    (net (code "56") (name "unconnected-(U12-PB3-Pad39)") (class "Default")
      (node (ref "U12") (pin "39") (pinfunction "PB3_39") (pintype "passive"))
    )
    (net (code "57") (name "unconnected-(U12-PB4-Pad40)") (class "Default")
      (node (ref "U12") (pin "40") (pinfunction "PB4_40") (pintype "passive"))
    )
    (net (code "58") (name "unconnected-(U12-PB5-Pad41)") (class "Default")
      (node (ref "U12") (pin "41") (pinfunction "PB5_41") (pintype "passive"))
    )
    (net (code "59") (name "unconnected-(U12-PB6-Pad42)") (class "Default")
      (node (ref "U12") (pin "42") (pinfunction "PB6_42") (pintype "passive"))
    )
    (net (code "60") (name "unconnected-(U12-PB10-Pad21)") (class "Default")
      (node (ref "U12") (pin "21") (pinfunction "PB10_21") (pintype "passive"))
    )
    (net (code "61") (name "unconnected-(U12-PB11-Pad22)") (class "Default")
      (node (ref "U12") (pin "22") (pinfunction "PB11_22") (pintype "passive"))
    )
    (net (code "62") (name "unconnected-(U12-PB13-Pad26)") (class "Default")
      (node (ref "U12") (pin "26") (pinfunction "PB13_26") (pintype "passive"))
    )
    (net (code "63") (name "unconnected-(U12-PB14-Pad27)") (class "Default")
      (node (ref "U12") (pin "27") (pinfunction "PB14_27") (pintype "passive"))
    )
    (net (code "64") (name "unconnected-(U12-PC13-TAMPER-RTC-Pad2)") (class "Default")
      (node (ref "U12") (pin "2") (pinfunction "PC13-TAMPER-RTC_2") (pintype "passive"))
    )
    (net (code "65") (name "unconnected-(U12-VBAT-Pad1)") (class "Default")
      (node (ref "U12") (pin "1") (pinfunction "VBAT_1") (pintype "passive"))
    )
  )
)
